# RSC.net
KiCad netlist of a schematic drawn in EAGLE
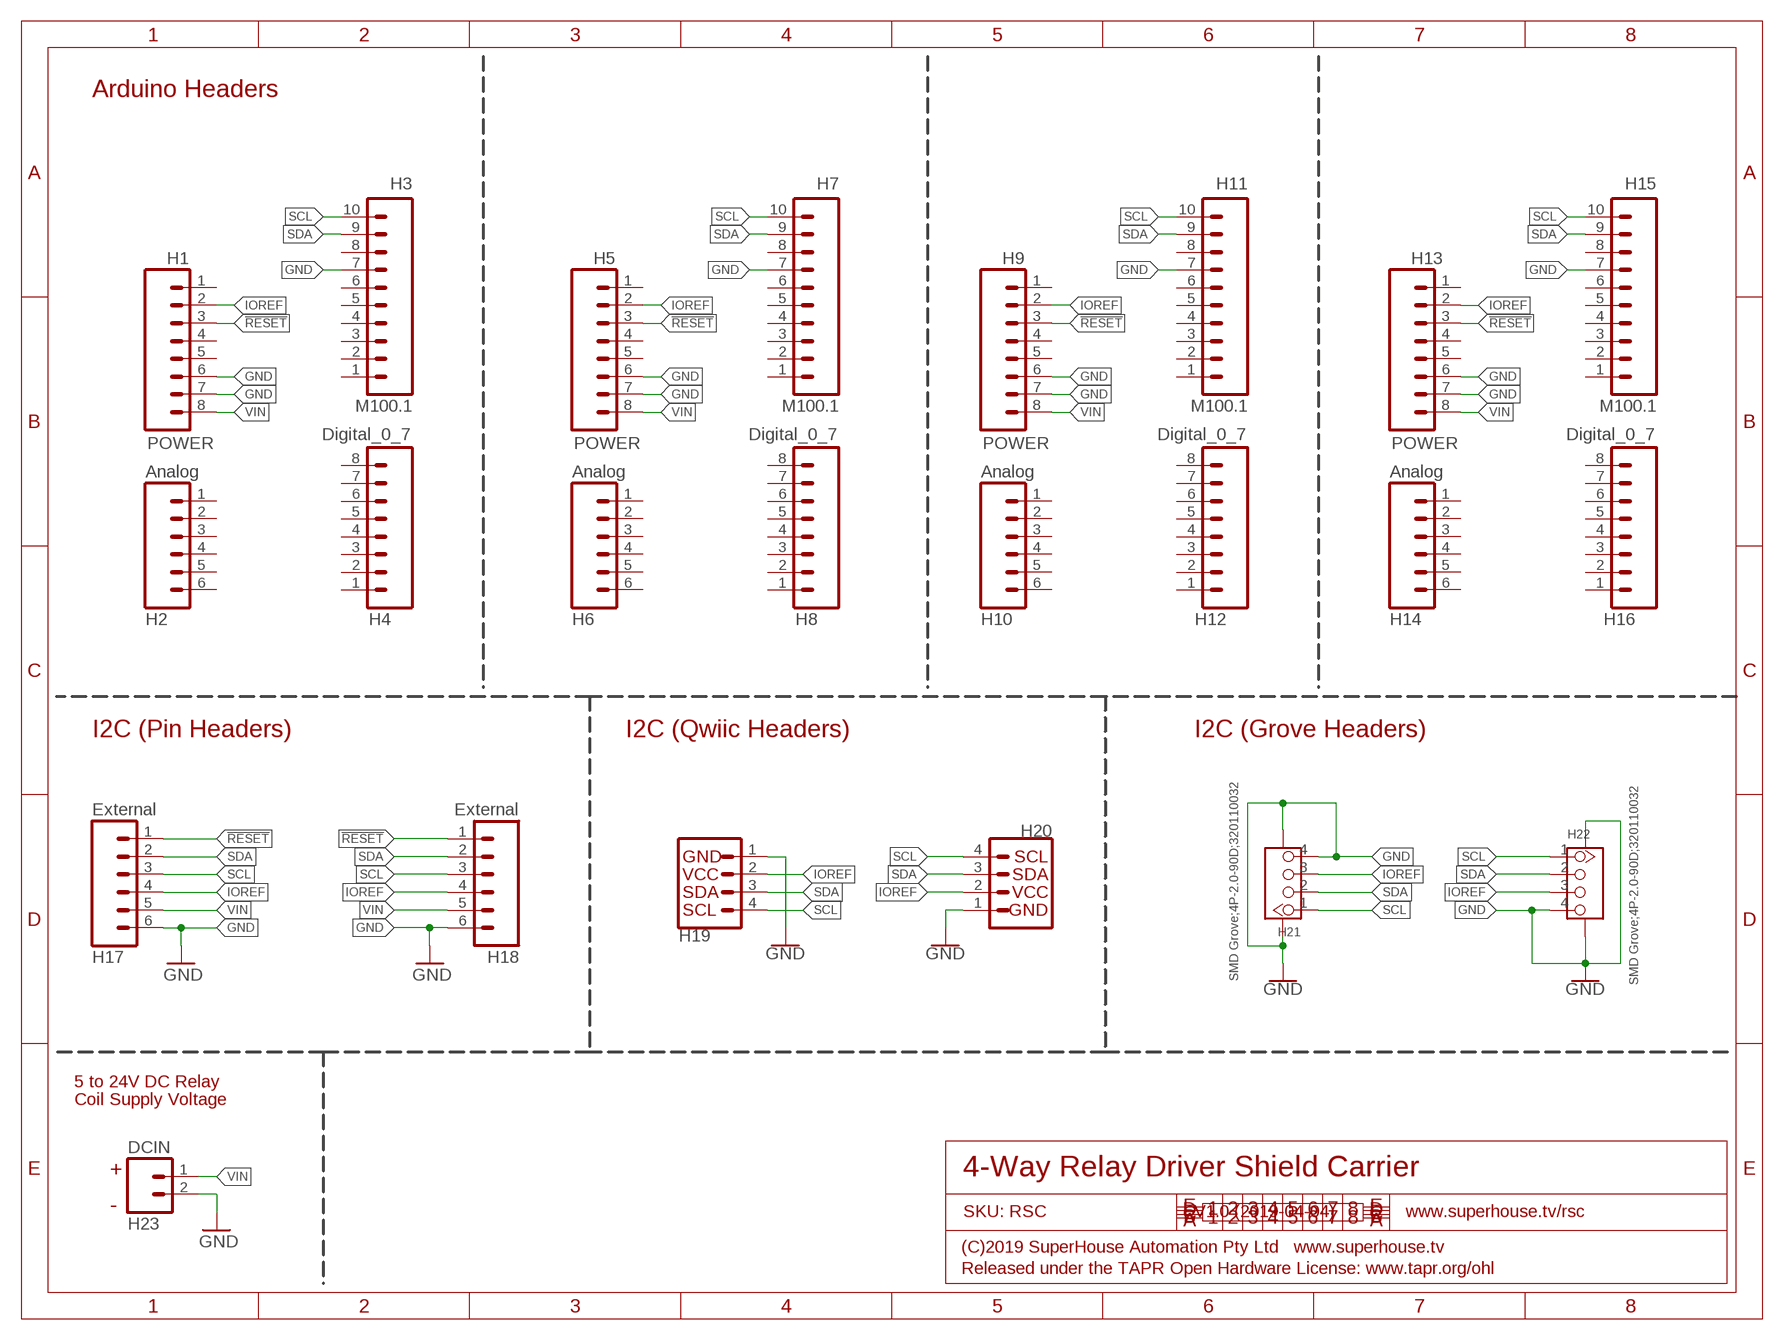
[diagram p0: schematic, sheet 1]

(export (version "E")
  (design (tool "Eeschema 10.0.6"))
  (components
    (comp (ref "H1")
      (value "POWER")
      (footprint "eagle-import:1X08")
      (libsource (lib "eagle-import") (part "M08"))
    )
    (comp (ref "H2")
      (value "Analog")
      (footprint "eagle-import:1X06")
      (libsource (lib "eagle-import") (part "M06SIP"))
    )
    (comp (ref "H3")
      (value "M100.1")
      (footprint "eagle-import:1X10")
      (libsource (lib "eagle-import") (part "M100.1"))
    )
    (comp (ref "H4")
      (value "Digital_0_7")
      (footprint "eagle-import:1X08")
      (libsource (lib "eagle-import") (part "M08"))
    )
    (comp (ref "H5")
      (value "POWER")
      (footprint "eagle-import:1X08")
      (libsource (lib "eagle-import") (part "M08"))
    )
    (comp (ref "H6")
      (value "Analog")
      (footprint "eagle-import:1X06")
      (libsource (lib "eagle-import") (part "M06SIP"))
    )
    (comp (ref "H7")
      (value "M100.1")
      (footprint "eagle-import:1X10")
      (libsource (lib "eagle-import") (part "M100.1"))
    )
    (comp (ref "H8")
      (value "Digital_0_7")
      (footprint "eagle-import:1X08")
      (libsource (lib "eagle-import") (part "M08"))
    )
    (comp (ref "H9")
      (value "POWER")
      (footprint "eagle-import:1X08")
      (libsource (lib "eagle-import") (part "M08"))
    )
    (comp (ref "H10")
      (value "Analog")
      (footprint "eagle-import:1X06")
      (libsource (lib "eagle-import") (part "M06SIP"))
    )
    (comp (ref "H11")
      (value "M100.1")
      (footprint "eagle-import:1X10")
      (libsource (lib "eagle-import") (part "M100.1"))
    )
    (comp (ref "H12")
      (value "Digital_0_7")
      (footprint "eagle-import:1X08")
      (libsource (lib "eagle-import") (part "M08"))
    )
    (comp (ref "H13")
      (value "POWER")
      (footprint "eagle-import:1X08")
      (libsource (lib "eagle-import") (part "M08"))
    )
    (comp (ref "H14")
      (value "Analog")
      (footprint "eagle-import:1X06")
      (libsource (lib "eagle-import") (part "M06SIP"))
    )
    (comp (ref "H15")
      (value "M100.1")
      (footprint "eagle-import:1X10")
      (libsource (lib "eagle-import") (part "M100.1"))
    )
    (comp (ref "H16")
      (value "Digital_0_7")
      (footprint "eagle-import:1X08")
      (libsource (lib "eagle-import") (part "M08"))
    )
    (comp (ref "H17")
      (value "External")
      (footprint "eagle-import:1X06")
      (libsource (lib "eagle-import") (part "M06SIP"))
    )
    (comp (ref "H18")
      (value "External")
      (footprint "eagle-import:1X06")
      (libsource (lib "eagle-import") (part "M06SIP"))
    )
    (comp (ref "H19")
      (value "QWIIC_CONNECTORJS-1MM")
      (footprint "eagle-import:1X04_1MM_RA")
      (libsource (lib "eagle-import") (part "QWIIC_CONNECTORJS-1MM"))
    )
    (comp (ref "H20")
      (value "QWIIC_CONNECTORJS-1MM")
      (footprint "eagle-import:1X04_1MM_RA")
      (libsource (lib "eagle-import") (part "QWIIC_CONNECTORJS-1MM"))
    )
    (comp (ref "H21")
      (value "SMD Grove;4P-2.0-90D;320110032")
      (footprint "eagle-import:HW4-SMD-2.0-90D")
      (libsource (lib "eagle-import") (part "GROVE-CONNECTOR-SMD'90D'"))
    )
    (comp (ref "H22")
      (value "SMD Grove;4P-2.0-90D;320110032")
      (footprint "eagle-import:HW4-SMD-2.0-90D")
      (libsource (lib "eagle-import") (part "GROVE-CONNECTOR-SMD'90D'"))
    )
    (comp (ref "H23")
      (value "DCIN")
      (footprint "eagle-import:SCREWTERMINAL-3.5MM-2")
      (libsource (lib "eagle-import") (part "M023.5MM"))
    )
  )
  (nets
    (net (code "1") (name "/~{RESET}") (class "Default")
      (node (ref "H1") (pin "3") (pinfunction "3_3") (pintype "passive"))
      (node (ref "H13") (pin "3") (pinfunction "3_3") (pintype "passive"))
      (node (ref "H17") (pin "1") (pinfunction "1_1") (pintype "passive"))
      (node (ref "H18") (pin "1") (pinfunction "1_1") (pintype "passive"))
      (node (ref "H5") (pin "3") (pinfunction "3_3") (pintype "passive"))
      (node (ref "H9") (pin "3") (pinfunction "3_3") (pintype "passive"))
    )
    (net (code "2") (name "GND") (class "Default")
      (node (ref "H1") (pin "6") (pinfunction "6_6") (pintype "passive"))
      (node (ref "H1") (pin "7") (pinfunction "7_7") (pintype "passive"))
      (node (ref "H11") (pin "7") (pinfunction "7_7") (pintype "passive"))
      (node (ref "H13") (pin "6") (pinfunction "6_6") (pintype "passive"))
      (node (ref "H13") (pin "7") (pinfunction "7_7") (pintype "passive"))
      (node (ref "H15") (pin "7") (pinfunction "7_7") (pintype "passive"))
      (node (ref "H17") (pin "6") (pinfunction "6_6") (pintype "passive"))
      (node (ref "H18") (pin "6") (pinfunction "6_6") (pintype "passive"))
      (node (ref "H19") (pin "1") (pinfunction "1_1") (pintype "power_in"))
      (node (ref "H20") (pin "1") (pinfunction "1_1") (pintype "power_in"))
      (node (ref "H21") (pin "4") (pinfunction "4_4") (pintype "bidirectional"))
      (node (ref "H21") (pin "SS1") (pinfunction "SS1_SS1") (pintype "bidirectional"))
      (node (ref "H21") (pin "SS2") (pinfunction "SS2_SS2") (pintype "bidirectional"))
      (node (ref "H22") (pin "4") (pinfunction "4_4") (pintype "bidirectional"))
      (node (ref "H22") (pin "SS1") (pinfunction "SS1_SS1") (pintype "bidirectional"))
      (node (ref "H22") (pin "SS2") (pinfunction "SS2_SS2") (pintype "bidirectional"))
      (node (ref "H23") (pin "2") (pinfunction "2_2") (pintype "passive"))
      (node (ref "H3") (pin "7") (pinfunction "7_7") (pintype "passive"))
      (node (ref "H5") (pin "6") (pinfunction "6_6") (pintype "passive"))
      (node (ref "H5") (pin "7") (pinfunction "7_7") (pintype "passive"))
      (node (ref "H7") (pin "7") (pinfunction "7_7") (pintype "passive"))
      (node (ref "H9") (pin "6") (pinfunction "6_6") (pintype "passive"))
      (node (ref "H9") (pin "7") (pinfunction "7_7") (pintype "passive"))
    )
    (net (code "3") (name "IOREF") (class "Default")
      (node (ref "H1") (pin "2") (pinfunction "2_2") (pintype "passive"))
      (node (ref "H13") (pin "2") (pinfunction "2_2") (pintype "passive"))
      (node (ref "H17") (pin "4") (pinfunction "4_4") (pintype "passive"))
      (node (ref "H18") (pin "4") (pinfunction "4_4") (pintype "passive"))
      (node (ref "H19") (pin "2") (pinfunction "2_2") (pintype "power_in"))
      (node (ref "H20") (pin "2") (pinfunction "2_2") (pintype "power_in"))
      (node (ref "H21") (pin "3") (pinfunction "3_3") (pintype "bidirectional"))
      (node (ref "H22") (pin "3") (pinfunction "3_3") (pintype "bidirectional"))
      (node (ref "H5") (pin "2") (pinfunction "2_2") (pintype "passive"))
      (node (ref "H9") (pin "2") (pinfunction "2_2") (pintype "passive"))
    )
    (net (code "4") (name "SCL") (class "Default")
      (node (ref "H11") (pin "10") (pinfunction "10_10") (pintype "passive"))
      (node (ref "H15") (pin "10") (pinfunction "10_10") (pintype "passive"))
      (node (ref "H17") (pin "3") (pinfunction "3_3") (pintype "passive"))
      (node (ref "H18") (pin "3") (pinfunction "3_3") (pintype "passive"))
      (node (ref "H19") (pin "4") (pinfunction "4_4") (pintype "passive"))
      (node (ref "H20") (pin "4") (pinfunction "4_4") (pintype "passive"))
      (node (ref "H21") (pin "1") (pinfunction "1_1") (pintype "bidirectional"))
      (node (ref "H22") (pin "1") (pinfunction "1_1") (pintype "bidirectional"))
      (node (ref "H3") (pin "10") (pinfunction "10_10") (pintype "passive"))
      (node (ref "H7") (pin "10") (pinfunction "10_10") (pintype "passive"))
    )
    (net (code "5") (name "SDA") (class "Default")
      (node (ref "H11") (pin "9") (pinfunction "9_9") (pintype "passive"))
      (node (ref "H15") (pin "9") (pinfunction "9_9") (pintype "passive"))
      (node (ref "H17") (pin "2") (pinfunction "2_2") (pintype "passive"))
      (node (ref "H18") (pin "2") (pinfunction "2_2") (pintype "passive"))
      (node (ref "H19") (pin "3") (pinfunction "3_3") (pintype "passive"))
      (node (ref "H20") (pin "3") (pinfunction "3_3") (pintype "passive"))
      (node (ref "H21") (pin "2") (pinfunction "2_2") (pintype "bidirectional"))
      (node (ref "H22") (pin "2") (pinfunction "2_2") (pintype "bidirectional"))
      (node (ref "H3") (pin "9") (pinfunction "9_9") (pintype "passive"))
      (node (ref "H7") (pin "9") (pinfunction "9_9") (pintype "passive"))
    )
    (net (code "6") (name "VIN") (class "Default")
      (node (ref "H1") (pin "8") (pinfunction "8_8") (pintype "passive"))
      (node (ref "H13") (pin "8") (pinfunction "8_8") (pintype "passive"))
      (node (ref "H17") (pin "5") (pinfunction "5_5") (pintype "passive"))
      (node (ref "H18") (pin "5") (pinfunction "5_5") (pintype "passive"))
      (node (ref "H23") (pin "1") (pinfunction "1_1") (pintype "passive"))
      (node (ref "H5") (pin "8") (pinfunction "8_8") (pintype "passive"))
      (node (ref "H9") (pin "8") (pinfunction "8_8") (pintype "passive"))
    )
    (net (code "7") (name "unconnected-(H1-Pad1)") (class "Default")
      (node (ref "H1") (pin "1") (pinfunction "1_1") (pintype "passive"))
    )
    (net (code "8") (name "unconnected-(H1-Pad4)") (class "Default")
      (node (ref "H1") (pin "4") (pinfunction "4_4") (pintype "passive"))
    )
    (net (code "9") (name "unconnected-(H1-Pad5)") (class "Default")
      (node (ref "H1") (pin "5") (pinfunction "5_5") (pintype "passive"))
    )
    (net (code "10") (name "unconnected-(H2-Pad1)") (class "Default")
      (node (ref "H2") (pin "1") (pinfunction "1_1") (pintype "passive"))
    )
    (net (code "11") (name "unconnected-(H2-Pad2)") (class "Default")
      (node (ref "H2") (pin "2") (pinfunction "2_2") (pintype "passive"))
    )
    (net (code "12") (name "unconnected-(H2-Pad3)") (class "Default")
      (node (ref "H2") (pin "3") (pinfunction "3_3") (pintype "passive"))
    )
    (net (code "13") (name "unconnected-(H2-Pad4)") (class "Default")
      (node (ref "H2") (pin "4") (pinfunction "4_4") (pintype "passive"))
    )
    (net (code "14") (name "unconnected-(H2-Pad5)") (class "Default")
      (node (ref "H2") (pin "5") (pinfunction "5_5") (pintype "passive"))
    )
    (net (code "15") (name "unconnected-(H2-Pad6)") (class "Default")
      (node (ref "H2") (pin "6") (pinfunction "6_6") (pintype "passive"))
    )
    (net (code "16") (name "unconnected-(H3-Pad1)") (class "Default")
      (node (ref "H3") (pin "1") (pinfunction "1_1") (pintype "passive"))
    )
    (net (code "17") (name "unconnected-(H3-Pad2)") (class "Default")
      (node (ref "H3") (pin "2") (pinfunction "2_2") (pintype "passive"))
    )
    (net (code "18") (name "unconnected-(H3-Pad3)") (class "Default")
      (node (ref "H3") (pin "3") (pinfunction "3_3") (pintype "passive"))
    )
    (net (code "19") (name "unconnected-(H3-Pad4)") (class "Default")
      (node (ref "H3") (pin "4") (pinfunction "4_4") (pintype "passive"))
    )
    (net (code "20") (name "unconnected-(H3-Pad5)") (class "Default")
      (node (ref "H3") (pin "5") (pinfunction "5_5") (pintype "passive"))
    )
    (net (code "21") (name "unconnected-(H3-Pad6)") (class "Default")
      (node (ref "H3") (pin "6") (pinfunction "6_6") (pintype "passive"))
    )
    (net (code "22") (name "unconnected-(H3-Pad8)") (class "Default")
      (node (ref "H3") (pin "8") (pinfunction "8_8") (pintype "passive"))
    )
    (net (code "23") (name "unconnected-(H4-Pad1)") (class "Default")
      (node (ref "H4") (pin "1") (pinfunction "1_1") (pintype "passive"))
    )
    (net (code "24") (name "unconnected-(H4-Pad2)") (class "Default")
      (node (ref "H4") (pin "2") (pinfunction "2_2") (pintype "passive"))
    )
    (net (code "25") (name "unconnected-(H4-Pad3)") (class "Default")
      (node (ref "H4") (pin "3") (pinfunction "3_3") (pintype "passive"))
    )
    (net (code "26") (name "unconnected-(H4-Pad4)") (class "Default")
      (node (ref "H4") (pin "4") (pinfunction "4_4") (pintype "passive"))
    )
    (net (code "27") (name "unconnected-(H4-Pad5)") (class "Default")
      (node (ref "H4") (pin "5") (pinfunction "5_5") (pintype "passive"))
    )
    (net (code "28") (name "unconnected-(H4-Pad6)") (class "Default")
      (node (ref "H4") (pin "6") (pinfunction "6_6") (pintype "passive"))
    )
    (net (code "29") (name "unconnected-(H4-Pad7)") (class "Default")
      (node (ref "H4") (pin "7") (pinfunction "7_7") (pintype "passive"))
    )
    (net (code "30") (name "unconnected-(H4-Pad8)") (class "Default")
      (node (ref "H4") (pin "8") (pinfunction "8_8") (pintype "passive"))
    )
    (net (code "31") (name "unconnected-(H5-Pad1)") (class "Default")
      (node (ref "H5") (pin "1") (pinfunction "1_1") (pintype "passive"))
    )
    (net (code "32") (name "unconnected-(H5-Pad4)") (class "Default")
      (node (ref "H5") (pin "4") (pinfunction "4_4") (pintype "passive"))
    )
    (net (code "33") (name "unconnected-(H5-Pad5)") (class "Default")
      (node (ref "H5") (pin "5") (pinfunction "5_5") (pintype "passive"))
    )
    (net (code "34") (name "unconnected-(H6-Pad1)") (class "Default")
      (node (ref "H6") (pin "1") (pinfunction "1_1") (pintype "passive"))
    )
    (net (code "35") (name "unconnected-(H6-Pad2)") (class "Default")
      (node (ref "H6") (pin "2") (pinfunction "2_2") (pintype "passive"))
    )
    (net (code "36") (name "unconnected-(H6-Pad3)") (class "Default")
      (node (ref "H6") (pin "3") (pinfunction "3_3") (pintype "passive"))
    )
    (net (code "37") (name "unconnected-(H6-Pad4)") (class "Default")
      (node (ref "H6") (pin "4") (pinfunction "4_4") (pintype "passive"))
    )
    (net (code "38") (name "unconnected-(H6-Pad5)") (class "Default")
      (node (ref "H6") (pin "5") (pinfunction "5_5") (pintype "passive"))
    )
    (net (code "39") (name "unconnected-(H6-Pad6)") (class "Default")
      (node (ref "H6") (pin "6") (pinfunction "6_6") (pintype "passive"))
    )
    (net (code "40") (name "unconnected-(H7-Pad1)") (class "Default")
      (node (ref "H7") (pin "1") (pinfunction "1_1") (pintype "passive"))
    )
    (net (code "41") (name "unconnected-(H7-Pad2)") (class "Default")
      (node (ref "H7") (pin "2") (pinfunction "2_2") (pintype "passive"))
    )
    (net (code "42") (name "unconnected-(H7-Pad3)") (class "Default")
      (node (ref "H7") (pin "3") (pinfunction "3_3") (pintype "passive"))
    )
    (net (code "43") (name "unconnected-(H7-Pad4)") (class "Default")
      (node (ref "H7") (pin "4") (pinfunction "4_4") (pintype "passive"))
    )
    (net (code "44") (name "unconnected-(H7-Pad5)") (class "Default")
      (node (ref "H7") (pin "5") (pinfunction "5_5") (pintype "passive"))
    )
    (net (code "45") (name "unconnected-(H7-Pad6)") (class "Default")
      (node (ref "H7") (pin "6") (pinfunction "6_6") (pintype "passive"))
    )
    (net (code "46") (name "unconnected-(H7-Pad8)") (class "Default")
      (node (ref "H7") (pin "8") (pinfunction "8_8") (pintype "passive"))
    )
    (net (code "47") (name "unconnected-(H8-Pad1)") (class "Default")
      (node (ref "H8") (pin "1") (pinfunction "1_1") (pintype "passive"))
    )
    (net (code "48") (name "unconnected-(H8-Pad2)") (class "Default")
      (node (ref "H8") (pin "2") (pinfunction "2_2") (pintype "passive"))
    )
    (net (code "49") (name "unconnected-(H8-Pad3)") (class "Default")
      (node (ref "H8") (pin "3") (pinfunction "3_3") (pintype "passive"))
    )
    (net (code "50") (name "unconnected-(H8-Pad4)") (class "Default")
      (node (ref "H8") (pin "4") (pinfunction "4_4") (pintype "passive"))
    )
    (net (code "51") (name "unconnected-(H8-Pad5)") (class "Default")
      (node (ref "H8") (pin "5") (pinfunction "5_5") (pintype "passive"))
    )
    (net (code "52") (name "unconnected-(H8-Pad6)") (class "Default")
      (node (ref "H8") (pin "6") (pinfunction "6_6") (pintype "passive"))
    )
    (net (code "53") (name "unconnected-(H8-Pad7)") (class "Default")
      (node (ref "H8") (pin "7") (pinfunction "7_7") (pintype "passive"))
    )
    (net (code "54") (name "unconnected-(H8-Pad8)") (class "Default")
      (node (ref "H8") (pin "8") (pinfunction "8_8") (pintype "passive"))
    )
    (net (code "55") (name "unconnected-(H9-Pad1)") (class "Default")
      (node (ref "H9") (pin "1") (pinfunction "1_1") (pintype "passive"))
    )
    (net (code "56") (name "unconnected-(H9-Pad4)") (class "Default")
      (node (ref "H9") (pin "4") (pinfunction "4_4") (pintype "passive"))
    )
    (net (code "57") (name "unconnected-(H9-Pad5)") (class "Default")
      (node (ref "H9") (pin "5") (pinfunction "5_5") (pintype "passive"))
    )
    (net (code "58") (name "unconnected-(H10-Pad1)") (class "Default")
      (node (ref "H10") (pin "1") (pinfunction "1_1") (pintype "passive"))
    )
    (net (code "59") (name "unconnected-(H10-Pad2)") (class "Default")
      (node (ref "H10") (pin "2") (pinfunction "2_2") (pintype "passive"))
    )
    (net (code "60") (name "unconnected-(H10-Pad3)") (class "Default")
      (node (ref "H10") (pin "3") (pinfunction "3_3") (pintype "passive"))
    )
    (net (code "61") (name "unconnected-(H10-Pad4)") (class "Default")
      (node (ref "H10") (pin "4") (pinfunction "4_4") (pintype "passive"))
    )
    (net (code "62") (name "unconnected-(H10-Pad5)") (class "Default")
      (node (ref "H10") (pin "5") (pinfunction "5_5") (pintype "passive"))
    )
    (net (code "63") (name "unconnected-(H10-Pad6)") (class "Default")
      (node (ref "H10") (pin "6") (pinfunction "6_6") (pintype "passive"))
    )
    (net (code "64") (name "unconnected-(H11-Pad1)") (class "Default")
      (node (ref "H11") (pin "1") (pinfunction "1_1") (pintype "passive"))
    )
    (net (code "65") (name "unconnected-(H11-Pad2)") (class "Default")
      (node (ref "H11") (pin "2") (pinfunction "2_2") (pintype "passive"))
    )
    (net (code "66") (name "unconnected-(H11-Pad3)") (class "Default")
      (node (ref "H11") (pin "3") (pinfunction "3_3") (pintype "passive"))
    )
    (net (code "67") (name "unconnected-(H11-Pad4)") (class "Default")
      (node (ref "H11") (pin "4") (pinfunction "4_4") (pintype "passive"))
    )
    (net (code "68") (name "unconnected-(H11-Pad5)") (class "Default")
      (node (ref "H11") (pin "5") (pinfunction "5_5") (pintype "passive"))
    )
    (net (code "69") (name "unconnected-(H11-Pad6)") (class "Default")
      (node (ref "H11") (pin "6") (pinfunction "6_6") (pintype "passive"))
    )
    (net (code "70") (name "unconnected-(H11-Pad8)") (class "Default")
      (node (ref "H11") (pin "8") (pinfunction "8_8") (pintype "passive"))
    )
    (net (code "71") (name "unconnected-(H12-Pad1)") (class "Default")
      (node (ref "H12") (pin "1") (pinfunction "1_1") (pintype "passive"))
    )
    (net (code "72") (name "unconnected-(H12-Pad2)") (class "Default")
      (node (ref "H12") (pin "2") (pinfunction "2_2") (pintype "passive"))
    )
    (net (code "73") (name "unconnected-(H12-Pad3)") (class "Default")
      (node (ref "H12") (pin "3") (pinfunction "3_3") (pintype "passive"))
    )
    (net (code "74") (name "unconnected-(H12-Pad4)") (class "Default")
      (node (ref "H12") (pin "4") (pinfunction "4_4") (pintype "passive"))
    )
    (net (code "75") (name "unconnected-(H12-Pad5)") (class "Default")
      (node (ref "H12") (pin "5") (pinfunction "5_5") (pintype "passive"))
    )
    (net (code "76") (name "unconnected-(H12-Pad6)") (class "Default")
      (node (ref "H12") (pin "6") (pinfunction "6_6") (pintype "passive"))
    )
    (net (code "77") (name "unconnected-(H12-Pad7)") (class "Default")
      (node (ref "H12") (pin "7") (pinfunction "7_7") (pintype "passive"))
    )
    (net (code "78") (name "unconnected-(H12-Pad8)") (class "Default")
      (node (ref "H12") (pin "8") (pinfunction "8_8") (pintype "passive"))
    )
    (net (code "79") (name "unconnected-(H13-Pad1)") (class "Default")
      (node (ref "H13") (pin "1") (pinfunction "1_1") (pintype "passive"))
    )
    (net (code "80") (name "unconnected-(H13-Pad4)") (class "Default")
      (node (ref "H13") (pin "4") (pinfunction "4_4") (pintype "passive"))
    )
    (net (code "81") (name "unconnected-(H13-Pad5)") (class "Default")
      (node (ref "H13") (pin "5") (pinfunction "5_5") (pintype "passive"))
    )
    (net (code "82") (name "unconnected-(H14-Pad1)") (class "Default")
      (node (ref "H14") (pin "1") (pinfunction "1_1") (pintype "passive"))
    )
    (net (code "83") (name "unconnected-(H14-Pad2)") (class "Default")
      (node (ref "H14") (pin "2") (pinfunction "2_2") (pintype "passive"))
    )
    (net (code "84") (name "unconnected-(H14-Pad3)") (class "Default")
      (node (ref "H14") (pin "3") (pinfunction "3_3") (pintype "passive"))
    )
    (net (code "85") (name "unconnected-(H14-Pad4)") (class "Default")
      (node (ref "H14") (pin "4") (pinfunction "4_4") (pintype "passive"))
    )
    (net (code "86") (name "unconnected-(H14-Pad5)") (class "Default")
      (node (ref "H14") (pin "5") (pinfunction "5_5") (pintype "passive"))
    )
    (net (code "87") (name "unconnected-(H14-Pad6)") (class "Default")
      (node (ref "H14") (pin "6") (pinfunction "6_6") (pintype "passive"))
    )
    (net (code "88") (name "unconnected-(H15-Pad1)") (class "Default")
      (node (ref "H15") (pin "1") (pinfunction "1_1") (pintype "passive"))
    )
    (net (code "89") (name "unconnected-(H15-Pad2)") (class "Default")
      (node (ref "H15") (pin "2") (pinfunction "2_2") (pintype "passive"))
    )
    (net (code "90") (name "unconnected-(H15-Pad3)") (class "Default")
      (node (ref "H15") (pin "3") (pinfunction "3_3") (pintype "passive"))
    )
    (net (code "91") (name "unconnected-(H15-Pad4)") (class "Default")
      (node (ref "H15") (pin "4") (pinfunction "4_4") (pintype "passive"))
    )
    (net (code "92") (name "unconnected-(H15-Pad5)") (class "Default")
      (node (ref "H15") (pin "5") (pinfunction "5_5") (pintype "passive"))
    )
    (net (code "93") (name "unconnected-(H15-Pad6)") (class "Default")
      (node (ref "H15") (pin "6") (pinfunction "6_6") (pintype "passive"))
    )
    (net (code "94") (name "unconnected-(H15-Pad8)") (class "Default")
      (node (ref "H15") (pin "8") (pinfunction "8_8") (pintype "passive"))
    )
    (net (code "95") (name "unconnected-(H16-Pad1)") (class "Default")
      (node (ref "H16") (pin "1") (pinfunction "1_1") (pintype "passive"))
    )
    (net (code "96") (name "unconnected-(H16-Pad2)") (class "Default")
      (node (ref "H16") (pin "2") (pinfunction "2_2") (pintype "passive"))
    )
    (net (code "97") (name "unconnected-(H16-Pad3)") (class "Default")
      (node (ref "H16") (pin "3") (pinfunction "3_3") (pintype "passive"))
    )
    (net (code "98") (name "unconnected-(H16-Pad4)") (class "Default")
      (node (ref "H16") (pin "4") (pinfunction "4_4") (pintype "passive"))
    )
    (net (code "99") (name "unconnected-(H16-Pad5)") (class "Default")
      (node (ref "H16") (pin "5") (pinfunction "5_5") (pintype "passive"))
    )
    (net (code "100") (name "unconnected-(H16-Pad6)") (class "Default")
      (node (ref "H16") (pin "6") (pinfunction "6_6") (pintype "passive"))
    )
    (net (code "101") (name "unconnected-(H16-Pad7)") (class "Default")
      (node (ref "H16") (pin "7") (pinfunction "7_7") (pintype "passive"))
    )
    (net (code "102") (name "unconnected-(H16-Pad8)") (class "Default")
      (node (ref "H16") (pin "8") (pinfunction "8_8") (pintype "passive"))
    )
  )
)
